# display.net
KiCad netlist of a schematic drawn in EAGLE
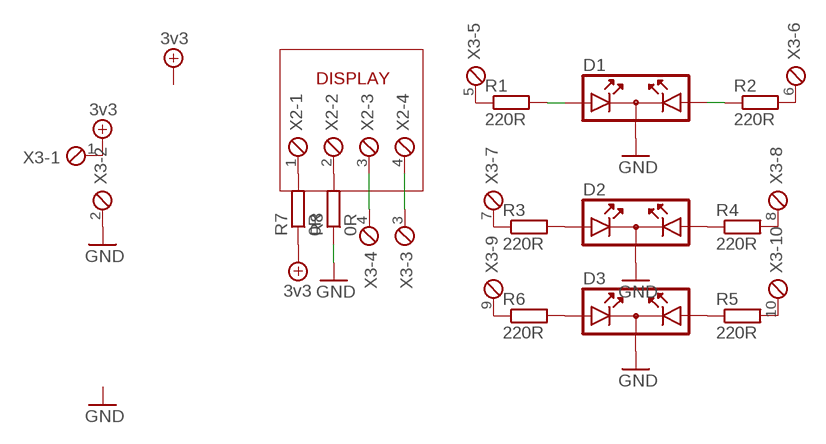
[diagram p0: schematic, sheet 1]

(export (version "E")
  (design (tool "Eeschema 10.0.6"))
  (components
    (comp (ref "D1")
      (value "DUOLED")
      (footprint "eagle-import:DUOLED")
      (libsource (lib "eagle-import") (part "DUOLED"))
    )
    (comp (ref "D2")
      (value "DUOLED")
      (footprint "eagle-import:DUOLED")
      (libsource (lib "eagle-import") (part "DUOLED"))
    )
    (comp (ref "D3")
      (value "DUOLED")
      (footprint "eagle-import:DUOLED")
      (libsource (lib "eagle-import") (part "DUOLED"))
    )
    (comp (ref "R1")
      (value "220R")
      (footprint "eagle-import:R0603")
      (libsource (lib "eagle-import") (part "R-EU_R0603"))
    )
    (comp (ref "R2")
      (value "220R")
      (footprint "eagle-import:R0603")
      (libsource (lib "eagle-import") (part "R-EU_R0603"))
    )
    (comp (ref "R3")
      (value "220R")
      (footprint "eagle-import:R0603")
      (libsource (lib "eagle-import") (part "R-EU_R0603"))
    )
    (comp (ref "R4")
      (value "220R")
      (footprint "eagle-import:R0603")
      (libsource (lib "eagle-import") (part "R-EU_R0603"))
    )
    (comp (ref "R5")
      (value "220R")
      (footprint "eagle-import:R0603")
      (libsource (lib "eagle-import") (part "R-EU_R0603"))
    )
    (comp (ref "R6")
      (value "220R")
      (footprint "eagle-import:R0603")
      (libsource (lib "eagle-import") (part "R-EU_R0603"))
    )
    (comp (ref "R7")
      (value "0R")
      (footprint "eagle-import:R0603")
      (libsource (lib "eagle-import") (part "R-EU_R0603"))
    )
    (comp (ref "R8")
      (value "0R")
      (footprint "eagle-import:R0603")
      (libsource (lib "eagle-import") (part "R-EU_R0603"))
    )
    (comp (ref "X2")
      (value "MPT4")
      (footprint "eagle-import:4POL254")
      (libsource (lib "eagle-import") (part "MPT4"))
    )
    (comp (ref "X3")
      (value "MPT10")
      (footprint "eagle-import:10POL254")
      (libsource (lib "eagle-import") (part "MPT10"))
    )
  )
  (nets
    (net (code "1") (name "3v3") (class "Default")
      (node (ref "R7") (pin "1") (pinfunction "1_1") (pintype "passive"))
      (node (ref "X3") (pin "1") (pinfunction "1_1") (pintype "passive"))
    )
    (net (code "2") (name "GND") (class "Default")
      (node (ref "D1") (pin "K") (pinfunction "K_K") (pintype "passive"))
      (node (ref "D2") (pin "K") (pinfunction "K_K") (pintype "passive"))
      (node (ref "D3") (pin "K") (pinfunction "K_K") (pintype "passive"))
      (node (ref "R8") (pin "1") (pinfunction "1_1") (pintype "passive"))
      (node (ref "X3") (pin "2") (pinfunction "1_2") (pintype "passive"))
    )
    (net (code "3") (name "Net-(D1-PadA1)") (class "Default")
      (node (ref "D1") (pin "A1") (pinfunction "A1_A1") (pintype "passive"))
      (node (ref "R1") (pin "2") (pinfunction "2_2") (pintype "passive"))
    )
    (net (code "4") (name "Net-(D1-PadA2)") (class "Default")
      (node (ref "D1") (pin "A2") (pinfunction "A2_A2") (pintype "passive"))
      (node (ref "R2") (pin "1") (pinfunction "1_1") (pintype "passive"))
    )
    (net (code "5") (name "Net-(D2-PadA1)") (class "Default")
      (node (ref "D2") (pin "A1") (pinfunction "A1_A1") (pintype "passive"))
      (node (ref "R3") (pin "2") (pinfunction "2_2") (pintype "passive"))
    )
    (net (code "6") (name "Net-(D2-PadA2)") (class "Default")
      (node (ref "D2") (pin "A2") (pinfunction "A2_A2") (pintype "passive"))
      (node (ref "R4") (pin "1") (pinfunction "1_1") (pintype "passive"))
    )
    (net (code "7") (name "Net-(D3-PadA1)") (class "Default")
      (node (ref "D3") (pin "A1") (pinfunction "A1_A1") (pintype "passive"))
      (node (ref "R6") (pin "2") (pinfunction "2_2") (pintype "passive"))
    )
    (net (code "8") (name "Net-(D3-PadA2)") (class "Default")
      (node (ref "D3") (pin "A2") (pinfunction "A2_A2") (pintype "passive"))
      (node (ref "R5") (pin "1") (pinfunction "1_1") (pintype "passive"))
    )
    (net (code "9") (name "Net-(R7-Pad2)") (class "Default")
      (node (ref "R7") (pin "2") (pinfunction "2_2") (pintype "passive"))
      (node (ref "X2") (pin "1") (pinfunction "1_1") (pintype "passive"))
    )
    (net (code "10") (name "Net-(X2B-1)") (class "Default")
      (node (ref "R8") (pin "2") (pinfunction "2_2") (pintype "passive"))
      (node (ref "X2") (pin "2") (pinfunction "1_2") (pintype "passive"))
    )
    (net (code "11") (name "Net-(X2C-1)") (class "Default")
      (node (ref "X2") (pin "3") (pinfunction "1_3") (pintype "passive"))
      (node (ref "X3") (pin "4") (pinfunction "1_4") (pintype "passive"))
    )
    (net (code "12") (name "Net-(X2D-1)") (class "Default")
      (node (ref "X2") (pin "4") (pinfunction "1_4") (pintype "passive"))
      (node (ref "X3") (pin "3") (pinfunction "1_3") (pintype "passive"))
    )
    (net (code "13") (name "Net-(X3B-1)") (class "Default")
      (node (ref "R5") (pin "2") (pinfunction "2_2") (pintype "passive"))
      (node (ref "X3") (pin "10") (pinfunction "1_10") (pintype "passive"))
    )
    (net (code "14") (name "Net-(X3F-1)") (class "Default")
      (node (ref "R1") (pin "1") (pinfunction "1_1") (pintype "passive"))
      (node (ref "X3") (pin "5") (pinfunction "1_5") (pintype "passive"))
    )
    (net (code "15") (name "Net-(X3G-1)") (class "Default")
      (node (ref "R2") (pin "2") (pinfunction "2_2") (pintype "passive"))
      (node (ref "X3") (pin "6") (pinfunction "1_6") (pintype "passive"))
    )
    (net (code "16") (name "Net-(X3H-1)") (class "Default")
      (node (ref "R3") (pin "1") (pinfunction "1_1") (pintype "passive"))
      (node (ref "X3") (pin "7") (pinfunction "1_7") (pintype "passive"))
    )
    (net (code "17") (name "Net-(X3I-1)") (class "Default")
      (node (ref "R4") (pin "2") (pinfunction "2_2") (pintype "passive"))
      (node (ref "X3") (pin "8") (pinfunction "1_8") (pintype "passive"))
    )
    (net (code "18") (name "Net-(X3J-1)") (class "Default")
      (node (ref "R6") (pin "1") (pinfunction "1_1") (pintype "passive"))
      (node (ref "X3") (pin "9") (pinfunction "1_9") (pintype "passive"))
    )
  )
)
